# dashboard.net
KiCad netlist of a schematic drawn in EAGLE
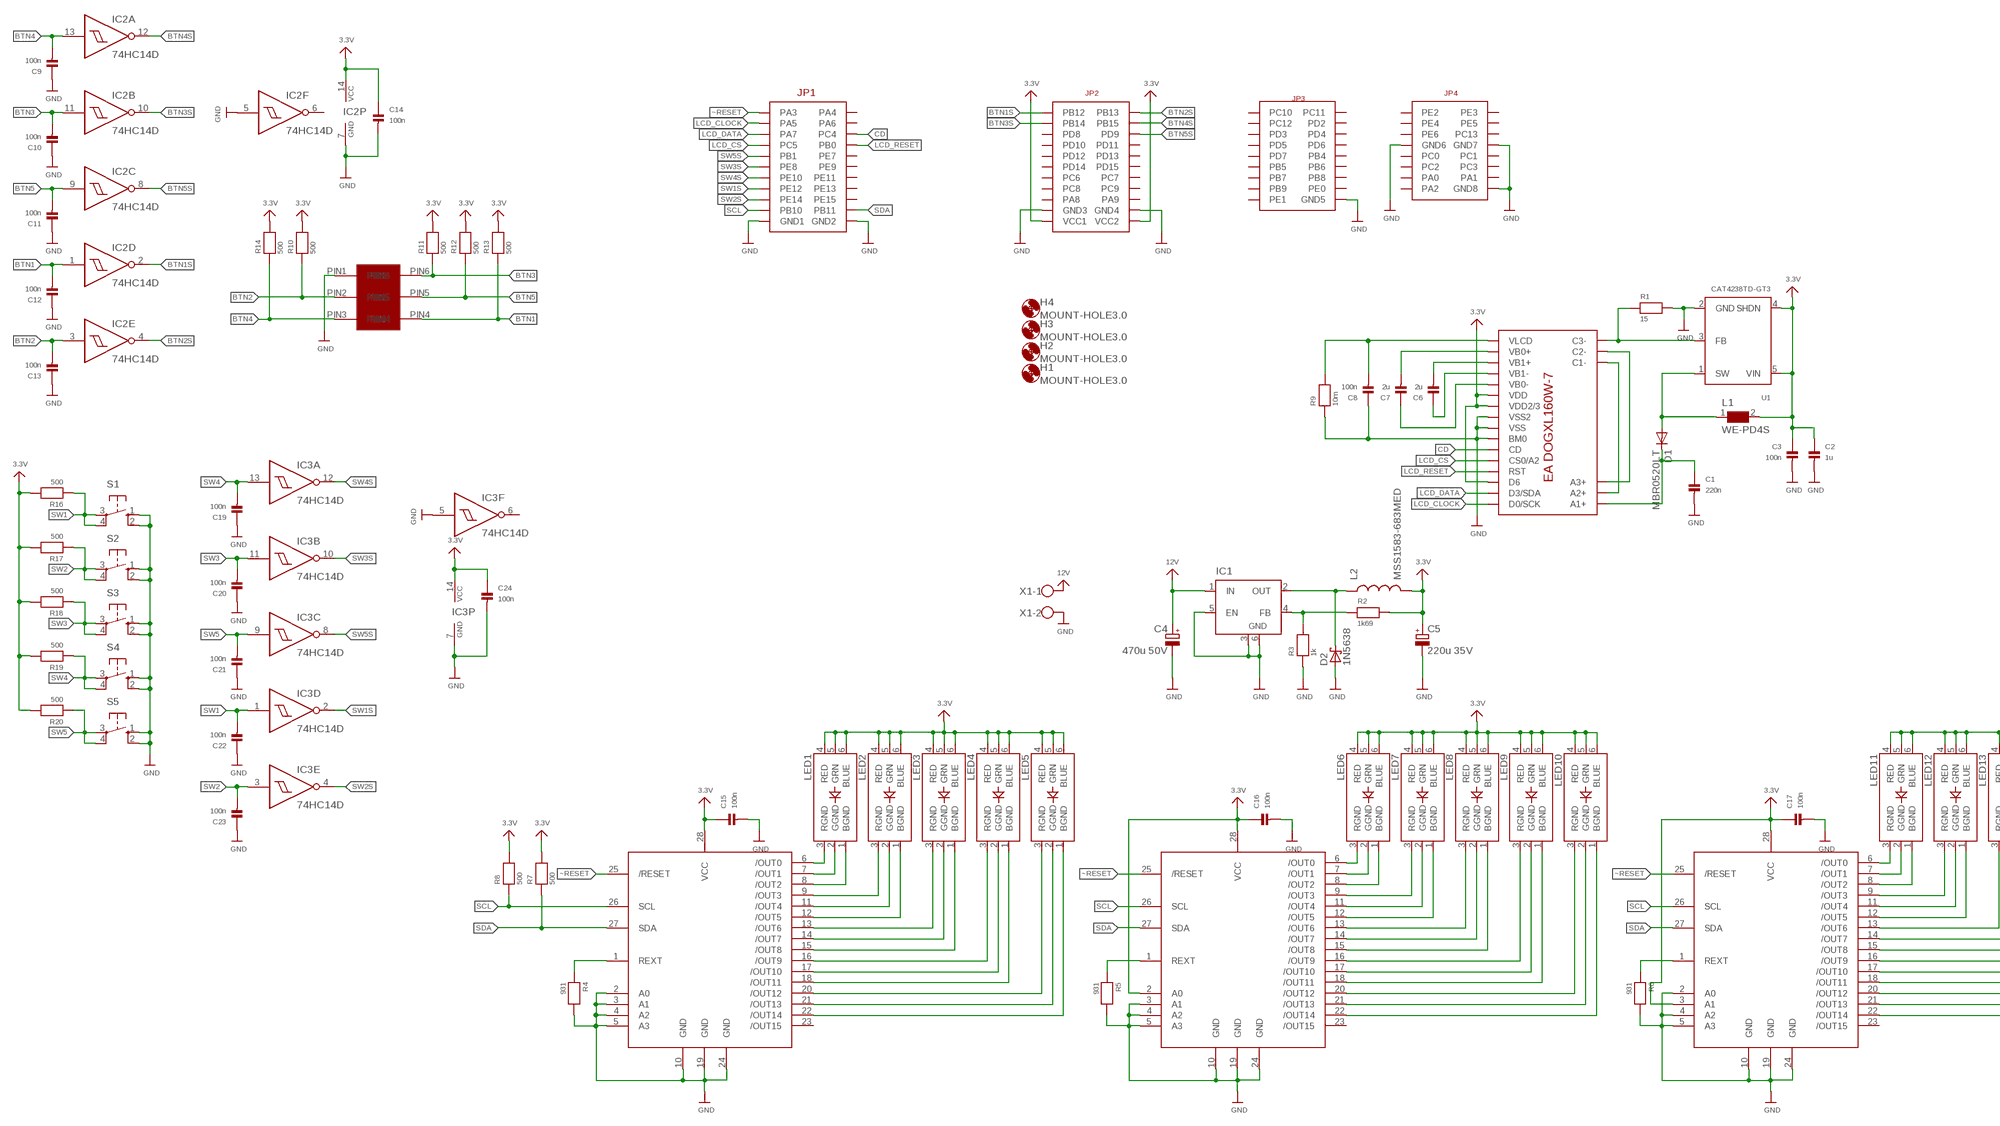
[diagram p0: schematic, sheet 1, part 1 of 2]
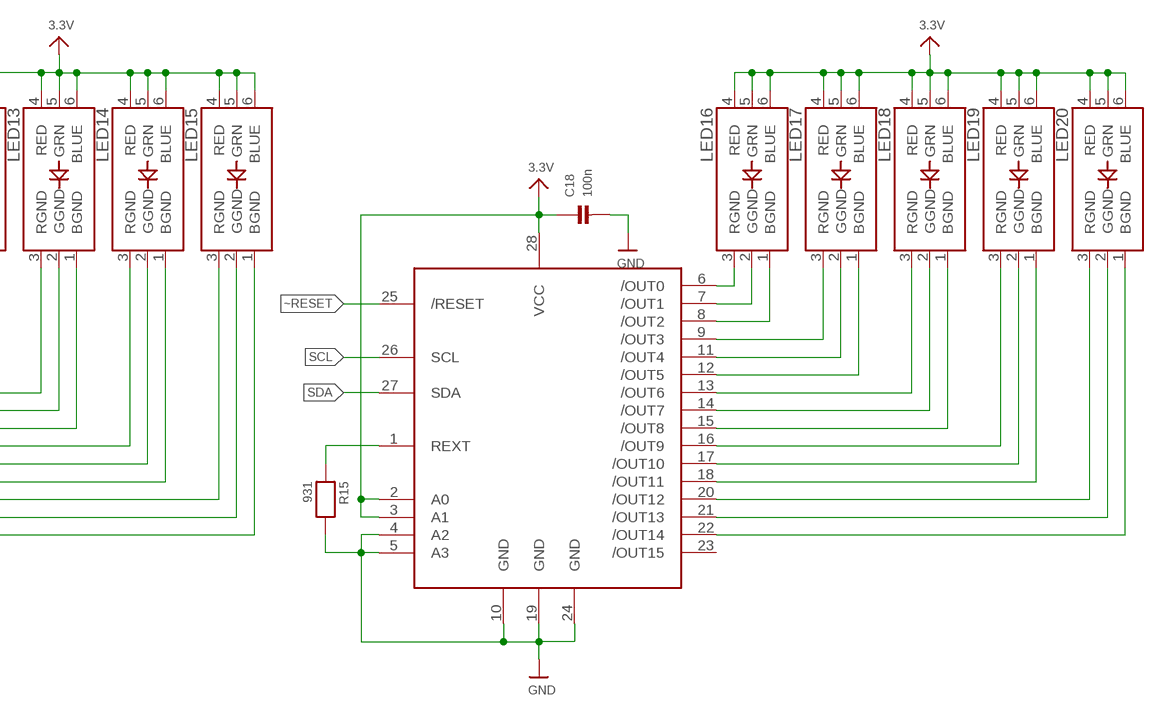
[diagram p1: schematic, sheet 1, part 2 of 2]

(export (version "E")
  (design (tool "Eeschema 10.0.6"))
  (components
    (comp (ref "C1")
      (value "220n")
      (footprint "eagle-import:_0805")
      (libsource (lib "eagle-import") (part "CAP_CERAMIC_0805"))
    )
    (comp (ref "C2")
      (value "1u")
      (footprint "eagle-import:_0805")
      (libsource (lib "eagle-import") (part "CAP_CERAMIC_0805"))
    )
    (comp (ref "C3")
      (value "100n")
      (footprint "eagle-import:_0603")
      (libsource (lib "eagle-import") (part "CAP_CERAMIC_0603"))
    )
    (comp (ref "C4")
      (value "470u 50V")
      (footprint "eagle-import:E5-13")
      (libsource (lib "eagle-import") (part "CPOL-EUE5-13"))
    )
    (comp (ref "C5")
      (value "220u 35V")
      (footprint "eagle-import:E3,5-8")
      (libsource (lib "eagle-import") (part "CPOL-EUE3.5-8"))
    )
    (comp (ref "C6")
      (value "2u")
      (footprint "eagle-import:_0805")
      (libsource (lib "eagle-import") (part "CAP_CERAMIC_0805"))
    )
    (comp (ref "C7")
      (value "2u")
      (footprint "eagle-import:_0805")
      (libsource (lib "eagle-import") (part "CAP_CERAMIC_0805"))
    )
    (comp (ref "C8")
      (value "100n")
      (footprint "eagle-import:_0603")
      (libsource (lib "eagle-import") (part "CAP_CERAMIC_0603"))
    )
    (comp (ref "C9")
      (value "100n")
      (footprint "eagle-import:_0603")
      (libsource (lib "eagle-import") (part "CAP_CERAMIC_0603"))
    )
    (comp (ref "C10")
      (value "100n")
      (footprint "eagle-import:_0603")
      (libsource (lib "eagle-import") (part "CAP_CERAMIC_0603"))
    )
    (comp (ref "C11")
      (value "100n")
      (footprint "eagle-import:_0603")
      (libsource (lib "eagle-import") (part "CAP_CERAMIC_0603"))
    )
    (comp (ref "C12")
      (value "100n")
      (footprint "eagle-import:_0603")
      (libsource (lib "eagle-import") (part "CAP_CERAMIC_0603"))
    )
    (comp (ref "C13")
      (value "100n")
      (footprint "eagle-import:_0603")
      (libsource (lib "eagle-import") (part "CAP_CERAMIC_0603"))
    )
    (comp (ref "C14")
      (value "100n")
      (footprint "eagle-import:_0603")
      (libsource (lib "eagle-import") (part "CAP_CERAMIC_0603"))
    )
    (comp (ref "C15")
      (value "100n")
      (footprint "eagle-import:_0603")
      (libsource (lib "eagle-import") (part "CAP_CERAMIC_0603"))
    )
    (comp (ref "C16")
      (value "100n")
      (footprint "eagle-import:_0603")
      (libsource (lib "eagle-import") (part "CAP_CERAMIC_0603"))
    )
    (comp (ref "C17")
      (value "100n")
      (footprint "eagle-import:_0603")
      (libsource (lib "eagle-import") (part "CAP_CERAMIC_0603"))
    )
    (comp (ref "C18")
      (value "100n")
      (footprint "eagle-import:_0603")
      (libsource (lib "eagle-import") (part "CAP_CERAMIC_0603"))
    )
    (comp (ref "C19")
      (value "100n")
      (footprint "eagle-import:_0603")
      (libsource (lib "eagle-import") (part "CAP_CERAMIC_0603"))
    )
    (comp (ref "C20")
      (value "100n")
      (footprint "eagle-import:_0603")
      (libsource (lib "eagle-import") (part "CAP_CERAMIC_0603"))
    )
    (comp (ref "C21")
      (value "100n")
      (footprint "eagle-import:_0603")
      (libsource (lib "eagle-import") (part "CAP_CERAMIC_0603"))
    )
    (comp (ref "C22")
      (value "100n")
      (footprint "eagle-import:_0603")
      (libsource (lib "eagle-import") (part "CAP_CERAMIC_0603"))
    )
    (comp (ref "C23")
      (value "100n")
      (footprint "eagle-import:_0603")
      (libsource (lib "eagle-import") (part "CAP_CERAMIC_0603"))
    )
    (comp (ref "C24")
      (value "100n")
      (footprint "eagle-import:_0603")
      (libsource (lib "eagle-import") (part "CAP_CERAMIC_0603"))
    )
    (comp (ref "D1")
      (value "MBR0520LT")
      (footprint "eagle-import:SOD123")
      (libsource (lib "eagle-import") (part "MBR0520LT"))
    )
    (comp (ref "D2")
      (value "1N5638")
      (footprint "eagle-import:DO13M")
      (libsource (lib "eagle-import") (part "1N5638"))
    )
    (comp (ref "H1")
      (value "MOUNT-HOLE3.0")
      (footprint "eagle-import:3,0")
      (libsource (lib "eagle-import") (part "MOUNT-HOLE3.0"))
    )
    (comp (ref "H2")
      (value "MOUNT-HOLE3.0")
      (footprint "eagle-import:3,0")
      (libsource (lib "eagle-import") (part "MOUNT-HOLE3.0"))
    )
    (comp (ref "H3")
      (value "MOUNT-HOLE3.0")
      (footprint "eagle-import:3,0")
      (libsource (lib "eagle-import") (part "MOUNT-HOLE3.0"))
    )
    (comp (ref "H4")
      (value "MOUNT-HOLE3.0")
      (footprint "eagle-import:3,0")
      (libsource (lib "eagle-import") (part "MOUNT-HOLE3.0"))
    )
    (comp (ref "IC1")
      (value "LM2596S")
      (footprint "eagle-import:TO263-5")
      (libsource (lib "eagle-import") (part "LM2596S"))
    )
    (comp (ref "IC2")
      (value "74HC14D")
      (footprint "eagle-import:SO14")
      (libsource (lib "eagle-import") (part "7414DHC"))
    )
    (comp (ref "IC3")
      (value "74HC14D")
      (footprint "eagle-import:SO14")
      (libsource (lib "eagle-import") (part "7414DHC"))
    )
    (comp (ref "L1")
      (value "WE-PD4S")
      (footprint "eagle-import:S")
      (fields (field (name "MPN") "7445501"))
      (libsource (lib "eagle-import") (part "WE-PD4_S-7445501"))
    )
    (comp (ref "L2")
      (value "MSS1583-683MED")
      (footprint "eagle-import:CDRH125")
      (libsource (lib "eagle-import") (part "INDUCTORPWR"))
    )
    (comp (ref "LED1")
      (value "LED_RGB_PLCC6CREE-CLV6A")
      (footprint "eagle-import:RGBLED_PLCC6")
      (libsource (lib "eagle-import") (part "LED_RGB_PLCC6CREE-CLV6A"))
    )
    (comp (ref "LED2")
      (value "LED_RGB_PLCC6CREE-CLV6A")
      (footprint "eagle-import:RGBLED_PLCC6")
      (libsource (lib "eagle-import") (part "LED_RGB_PLCC6CREE-CLV6A"))
    )
    (comp (ref "LED3")
      (value "LED_RGB_PLCC6CREE-CLV6A")
      (footprint "eagle-import:RGBLED_PLCC6")
      (libsource (lib "eagle-import") (part "LED_RGB_PLCC6CREE-CLV6A"))
    )
    (comp (ref "LED4")
      (value "LED_RGB_PLCC6CREE-CLV6A")
      (footprint "eagle-import:RGBLED_PLCC6")
      (libsource (lib "eagle-import") (part "LED_RGB_PLCC6CREE-CLV6A"))
    )
    (comp (ref "LED5")
      (value "LED_RGB_PLCC6CREE-CLV6A")
      (footprint "eagle-import:RGBLED_PLCC6")
      (libsource (lib "eagle-import") (part "LED_RGB_PLCC6CREE-CLV6A"))
    )
    (comp (ref "LED6")
      (value "LED_RGB_PLCC6CREE-CLV6A")
      (footprint "eagle-import:RGBLED_PLCC6")
      (libsource (lib "eagle-import") (part "LED_RGB_PLCC6CREE-CLV6A"))
    )
    (comp (ref "LED7")
      (value "LED_RGB_PLCC6CREE-CLV6A")
      (footprint "eagle-import:RGBLED_PLCC6")
      (libsource (lib "eagle-import") (part "LED_RGB_PLCC6CREE-CLV6A"))
    )
    (comp (ref "LED8")
      (value "LED_RGB_PLCC6CREE-CLV6A")
      (footprint "eagle-import:RGBLED_PLCC6")
      (libsource (lib "eagle-import") (part "LED_RGB_PLCC6CREE-CLV6A"))
    )
    (comp (ref "LED9")
      (value "LED_RGB_PLCC6CREE-CLV6A")
      (footprint "eagle-import:RGBLED_PLCC6")
      (libsource (lib "eagle-import") (part "LED_RGB_PLCC6CREE-CLV6A"))
    )
    (comp (ref "LED10")
      (value "LED_RGB_PLCC6CREE-CLV6A")
      (footprint "eagle-import:RGBLED_PLCC6")
      (libsource (lib "eagle-import") (part "LED_RGB_PLCC6CREE-CLV6A"))
    )
    (comp (ref "LED11")
      (value "LED_RGB_PLCC6CREE-CLV6A")
      (footprint "eagle-import:RGBLED_PLCC6")
      (libsource (lib "eagle-import") (part "LED_RGB_PLCC6CREE-CLV6A"))
    )
    (comp (ref "LED12")
      (value "LED_RGB_PLCC6CREE-CLV6A")
      (footprint "eagle-import:RGBLED_PLCC6")
      (libsource (lib "eagle-import") (part "LED_RGB_PLCC6CREE-CLV6A"))
    )
    (comp (ref "LED13")
      (value "LED_RGB_PLCC6CREE-CLV6A")
      (footprint "eagle-import:RGBLED_PLCC6")
      (libsource (lib "eagle-import") (part "LED_RGB_PLCC6CREE-CLV6A"))
    )
    (comp (ref "LED14")
      (value "LED_RGB_PLCC6CREE-CLV6A")
      (footprint "eagle-import:RGBLED_PLCC6")
      (libsource (lib "eagle-import") (part "LED_RGB_PLCC6CREE-CLV6A"))
    )
    (comp (ref "LED15")
      (value "LED_RGB_PLCC6CREE-CLV6A")
      (footprint "eagle-import:RGBLED_PLCC6")
      (libsource (lib "eagle-import") (part "LED_RGB_PLCC6CREE-CLV6A"))
    )
    (comp (ref "LED16")
      (value "LED_RGB_PLCC6CREE-CLV6A")
      (footprint "eagle-import:RGBLED_PLCC6")
      (libsource (lib "eagle-import") (part "LED_RGB_PLCC6CREE-CLV6A"))
    )
    (comp (ref "LED17")
      (value "LED_RGB_PLCC6CREE-CLV6A")
      (footprint "eagle-import:RGBLED_PLCC6")
      (libsource (lib "eagle-import") (part "LED_RGB_PLCC6CREE-CLV6A"))
    )
    (comp (ref "LED18")
      (value "LED_RGB_PLCC6CREE-CLV6A")
      (footprint "eagle-import:RGBLED_PLCC6")
      (libsource (lib "eagle-import") (part "LED_RGB_PLCC6CREE-CLV6A"))
    )
    (comp (ref "LED19")
      (value "LED_RGB_PLCC6CREE-CLV6A")
      (footprint "eagle-import:RGBLED_PLCC6")
      (libsource (lib "eagle-import") (part "LED_RGB_PLCC6CREE-CLV6A"))
    )
    (comp (ref "LED20")
      (value "LED_RGB_PLCC6CREE-CLV6A")
      (footprint "eagle-import:RGBLED_PLCC6")
      (libsource (lib "eagle-import") (part "LED_RGB_PLCC6CREE-CLV6A"))
    )
    (comp (ref "R1")
      (value "15")
      (footprint "eagle-import:_0603")
      (libsource (lib "eagle-import") (part "RESISTOR_0603"))
    )
    (comp (ref "R2")
      (value "1k69")
      (footprint "eagle-import:_0603")
      (libsource (lib "eagle-import") (part "RESISTOR_0603"))
    )
    (comp (ref "R3")
      (value "1k")
      (footprint "eagle-import:_0603")
      (libsource (lib "eagle-import") (part "RESISTOR_0603"))
    )
    (comp (ref "R4")
      (value "931")
      (footprint "eagle-import:_0603")
      (libsource (lib "eagle-import") (part "RESISTOR_0603"))
    )
    (comp (ref "R5")
      (value "931")
      (footprint "eagle-import:_0603")
      (libsource (lib "eagle-import") (part "RESISTOR_0603"))
    )
    (comp (ref "R6")
      (value "931")
      (footprint "eagle-import:_0603")
      (libsource (lib "eagle-import") (part "RESISTOR_0603"))
    )
    (comp (ref "R7")
      (value "500")
      (footprint "eagle-import:_0603")
      (libsource (lib "eagle-import") (part "RESISTOR_0603"))
    )
    (comp (ref "R8")
      (value "500")
      (footprint "eagle-import:_0603")
      (libsource (lib "eagle-import") (part "RESISTOR_0603"))
    )
    (comp (ref "R9")
      (value "10m")
      (footprint "eagle-import:_0805")
      (libsource (lib "eagle-import") (part "RESISTOR_0805"))
    )
    (comp (ref "R10")
      (value "500")
      (footprint "eagle-import:_0603")
      (libsource (lib "eagle-import") (part "RESISTOR_0603"))
    )
    (comp (ref "R11")
      (value "500")
      (footprint "eagle-import:_0603")
      (libsource (lib "eagle-import") (part "RESISTOR_0603"))
    )
    (comp (ref "R12")
      (value "500")
      (footprint "eagle-import:_0603")
      (libsource (lib "eagle-import") (part "RESISTOR_0603"))
    )
    (comp (ref "R13")
      (value "500")
      (footprint "eagle-import:_0603")
      (libsource (lib "eagle-import") (part "RESISTOR_0603"))
    )
    (comp (ref "R14")
      (value "500")
      (footprint "eagle-import:_0603")
      (libsource (lib "eagle-import") (part "RESISTOR_0603"))
    )
    (comp (ref "R15")
      (value "931")
      (footprint "eagle-import:_0603")
      (libsource (lib "eagle-import") (part "RESISTOR_0603"))
    )
    (comp (ref "R16")
      (value "500")
      (footprint "eagle-import:_0603")
      (libsource (lib "eagle-import") (part "RESISTOR_0603"))
    )
    (comp (ref "R17")
      (value "500")
      (footprint "eagle-import:_0603")
      (libsource (lib "eagle-import") (part "RESISTOR_0603"))
    )
    (comp (ref "R18")
      (value "500")
      (footprint "eagle-import:_0603")
      (libsource (lib "eagle-import") (part "RESISTOR_0603"))
    )
    (comp (ref "R19")
      (value "500")
      (footprint "eagle-import:_0603")
      (libsource (lib "eagle-import") (part "RESISTOR_0603"))
    )
    (comp (ref "R20")
      (value "500")
      (footprint "eagle-import:_0603")
      (libsource (lib "eagle-import") (part "RESISTOR_0603"))
    )
    (comp (ref "S1")
      (value "10-XX")
      (footprint "eagle-import:B3F-10XX")
      (fields (field (name "MPN") "B3F-1000"))
      (libsource (lib "eagle-import") (part "10-XX"))
    )
    (comp (ref "S2")
      (value "10-XX")
      (footprint "eagle-import:B3F-10XX")
      (fields (field (name "MPN") "B3F-1000"))
      (libsource (lib "eagle-import") (part "10-XX"))
    )
    (comp (ref "S3")
      (value "10-XX")
      (footprint "eagle-import:B3F-10XX")
      (fields (field (name "MPN") "B3F-1000"))
      (libsource (lib "eagle-import") (part "10-XX"))
    )
    (comp (ref "S4")
      (value "10-XX")
      (footprint "eagle-import:B3F-10XX")
      (fields (field (name "MPN") "B3F-1000"))
      (libsource (lib "eagle-import") (part "10-XX"))
    )
    (comp (ref "S5")
      (value "10-XX")
      (footprint "eagle-import:B3F-10XX")
      (fields
        (field (name "MPN") "B3F-1000")
        (field (name "MPN_1") "B3F-1000")
        (field (name "OC_FARNELL") "176432")
        (field (name "OC_NEWARK") "36M3542")
      )
      (libsource (lib "eagle-import") (part "10-XX"))
    )
    (comp (ref "U$1")
      (value "CPU-BOARD")
      (footprint "eagle-import:CPU-BOARD-JP1")
      (libsource (lib "eagle-import") (part "CPU-BOARD"))
    )
    (comp (ref "U$10")
      (value "EA-DOGXL160W-7")
      (footprint "eagle-import:EA-DOGXL160W-7")
      (libsource (lib "eagle-import") (part "EA-DOGXL160W-7"))
    )
    (comp (ref "U$30")
      (value "TLC59116")
      (footprint "eagle-import:TSSOP28")
      (libsource (lib "eagle-import") (part "TLC59116"))
    )
    (comp (ref "U$33")
      (value "TLC59116")
      (footprint "eagle-import:TSSOP28")
      (libsource (lib "eagle-import") (part "TLC59116"))
    )
    (comp (ref "U$36")
      (value "TLC59116")
      (footprint "eagle-import:TSSOP28")
      (libsource (lib "eagle-import") (part "TLC59116"))
    )
    (comp (ref "U$42")
      (value "MICROFIT6")
      (footprint "eagle-import:MICROFIT6SOCK")
      (libsource (lib "eagle-import") (part "MICROFIT6"))
    )
    (comp (ref "U$51")
      (value "TLC59116")
      (footprint "eagle-import:TSSOP28")
      (libsource (lib "eagle-import") (part "TLC59116"))
    )
    (comp (ref "U1")
      (value "CAT4238TD-GT3")
      (footprint "eagle-import:SOT23-5")
      (libsource (lib "eagle-import") (part "FAN5331"))
    )
    (comp (ref "X1")
      (value "W237-102")
      (footprint "eagle-import:W237-102")
      (fields (field (name "MPN") "237-102"))
      (libsource (lib "eagle-import") (part "W237-102"))
    )
  )
  (nets
    (net (code "1") (name "/~{RESET}") (class "Default")
      (node (ref "U$1") (pin "P$1") (pinfunction "PA3_P$1") (pintype "bidirectional"))
      (node (ref "U$30") (pin "25") (pinfunction "/RESET_25") (pintype "bidirectional"))
      (node (ref "U$33") (pin "25") (pinfunction "/RESET_25") (pintype "bidirectional"))
      (node (ref "U$36") (pin "25") (pinfunction "/RESET_25") (pintype "bidirectional"))
      (node (ref "U$51") (pin "25") (pinfunction "/RESET_25") (pintype "bidirectional"))
    )
    (net (code "2") (name "3.3V") (class "Default")
      (node (ref "C14") (pin "1") (pinfunction "P$1_1") (pintype "passive"))
      (node (ref "C15") (pin "1") (pinfunction "P$1_1") (pintype "passive"))
      (node (ref "C16") (pin "1") (pinfunction "P$1_1") (pintype "passive"))
      (node (ref "C17") (pin "1") (pinfunction "P$1_1") (pintype "passive"))
      (node (ref "C18") (pin "1") (pinfunction "P$1_1") (pintype "passive"))
      (node (ref "C2") (pin "1") (pinfunction "P$1_1") (pintype "passive"))
      (node (ref "C24") (pin "1") (pinfunction "P$1_1") (pintype "passive"))
      (node (ref "C3") (pin "1") (pinfunction "P$1_1") (pintype "passive"))
      (node (ref "C5") (pin "+") (pinfunction "+_+") (pintype "passive"))
      (node (ref "IC2") (pin "14") (pinfunction "VCC_14") (pintype "power_in"))
      (node (ref "IC3") (pin "14") (pinfunction "VCC_14") (pintype "power_in"))
      (node (ref "L1") (pin "2") (pinfunction "2_2") (pintype "passive"))
      (node (ref "L2") (pin "2") (pinfunction "2_2") (pintype "passive"))
      (node (ref "LED1") (pin "4") (pinfunction "RED_4") (pintype "bidirectional"))
      (node (ref "LED1") (pin "5") (pinfunction "GRN_5") (pintype "bidirectional"))
      (node (ref "LED1") (pin "6") (pinfunction "BLUE_6") (pintype "bidirectional"))
      (node (ref "LED10") (pin "4") (pinfunction "RED_4") (pintype "bidirectional"))
      (node (ref "LED10") (pin "5") (pinfunction "GRN_5") (pintype "bidirectional"))
      (node (ref "LED10") (pin "6") (pinfunction "BLUE_6") (pintype "bidirectional"))
      (node (ref "LED11") (pin "4") (pinfunction "RED_4") (pintype "bidirectional"))
      (node (ref "LED11") (pin "5") (pinfunction "GRN_5") (pintype "bidirectional"))
      (node (ref "LED11") (pin "6") (pinfunction "BLUE_6") (pintype "bidirectional"))
      (node (ref "LED12") (pin "4") (pinfunction "RED_4") (pintype "bidirectional"))
      (node (ref "LED12") (pin "5") (pinfunction "GRN_5") (pintype "bidirectional"))
      (node (ref "LED12") (pin "6") (pinfunction "BLUE_6") (pintype "bidirectional"))
      (node (ref "LED13") (pin "4") (pinfunction "RED_4") (pintype "bidirectional"))
      (node (ref "LED13") (pin "5") (pinfunction "GRN_5") (pintype "bidirectional"))
      (node (ref "LED13") (pin "6") (pinfunction "BLUE_6") (pintype "bidirectional"))
      (node (ref "LED14") (pin "4") (pinfunction "RED_4") (pintype "bidirectional"))
      (node (ref "LED14") (pin "5") (pinfunction "GRN_5") (pintype "bidirectional"))
      (node (ref "LED14") (pin "6") (pinfunction "BLUE_6") (pintype "bidirectional"))
      (node (ref "LED15") (pin "4") (pinfunction "RED_4") (pintype "bidirectional"))
      (node (ref "LED15") (pin "5") (pinfunction "GRN_5") (pintype "bidirectional"))
      (node (ref "LED15") (pin "6") (pinfunction "BLUE_6") (pintype "bidirectional"))
      (node (ref "LED16") (pin "4") (pinfunction "RED_4") (pintype "bidirectional"))
      (node (ref "LED16") (pin "5") (pinfunction "GRN_5") (pintype "bidirectional"))
      (node (ref "LED16") (pin "6") (pinfunction "BLUE_6") (pintype "bidirectional"))
      (node (ref "LED17") (pin "4") (pinfunction "RED_4") (pintype "bidirectional"))
      (node (ref "LED17") (pin "5") (pinfunction "GRN_5") (pintype "bidirectional"))
      (node (ref "LED17") (pin "6") (pinfunction "BLUE_6") (pintype "bidirectional"))
      (node (ref "LED18") (pin "4") (pinfunction "RED_4") (pintype "bidirectional"))
      (node (ref "LED18") (pin "5") (pinfunction "GRN_5") (pintype "bidirectional"))
      (node (ref "LED18") (pin "6") (pinfunction "BLUE_6") (pintype "bidirectional"))
      (node (ref "LED19") (pin "4") (pinfunction "RED_4") (pintype "bidirectional"))
      (node (ref "LED19") (pin "5") (pinfunction "GRN_5") (pintype "bidirectional"))
      (node (ref "LED19") (pin "6") (pinfunction "BLUE_6") (pintype "bidirectional"))
      (node (ref "LED2") (pin "4") (pinfunction "RED_4") (pintype "bidirectional"))
      (node (ref "LED2") (pin "5") (pinfunction "GRN_5") (pintype "bidirectional"))
      (node (ref "LED2") (pin "6") (pinfunction "BLUE_6") (pintype "bidirectional"))
      (node (ref "LED20") (pin "4") (pinfunction "RED_4") (pintype "bidirectional"))
      (node (ref "LED20") (pin "5") (pinfunction "GRN_5") (pintype "bidirectional"))
      (node (ref "LED20") (pin "6") (pinfunction "BLUE_6") (pintype "bidirectional"))
      (node (ref "LED3") (pin "4") (pinfunction "RED_4") (pintype "bidirectional"))
      (node (ref "LED3") (pin "5") (pinfunction "GRN_5") (pintype "bidirectional"))
      (node (ref "LED3") (pin "6") (pinfunction "BLUE_6") (pintype "bidirectional"))
      (node (ref "LED4") (pin "4") (pinfunction "RED_4") (pintype "bidirectional"))
      (node (ref "LED4") (pin "5") (pinfunction "GRN_5") (pintype "bidirectional"))
      (node (ref "LED4") (pin "6") (pinfunction "BLUE_6") (pintype "bidirectional"))
      (node (ref "LED5") (pin "4") (pinfunction "RED_4") (pintype "bidirectional"))
      (node (ref "LED5") (pin "5") (pinfunction "GRN_5") (pintype "bidirectional"))
      (node (ref "LED5") (pin "6") (pinfunction "BLUE_6") (pintype "bidirectional"))
      (node (ref "LED6") (pin "4") (pinfunction "RED_4") (pintype "bidirectional"))
      (node (ref "LED6") (pin "5") (pinfunction "GRN_5") (pintype "bidirectional"))
      (node (ref "LED6") (pin "6") (pinfunction "BLUE_6") (pintype "bidirectional"))
      (node (ref "LED7") (pin "4") (pinfunction "RED_4") (pintype "bidirectional"))
      (node (ref "LED7") (pin "5") (pinfunction "GRN_5") (pintype "bidirectional"))
      (node (ref "LED7") (pin "6") (pinfunction "BLUE_6") (pintype "bidirectional"))
      (node (ref "LED8") (pin "4") (pinfunction "RED_4") (pintype "bidirectional"))
      (node (ref "LED8") (pin "5") (pinfunction "GRN_5") (pintype "bidirectional"))
      (node (ref "LED8") (pin "6") (pinfunction "BLUE_6") (pintype "bidirectional"))
      (node (ref "LED9") (pin "4") (pinfunction "RED_4") (pintype "bidirectional"))
      (node (ref "LED9") (pin "5") (pinfunction "GRN_5") (pintype "bidirectional"))
      (node (ref "LED9") (pin "6") (pinfunction "BLUE_6") (pintype "bidirectional"))
      (node (ref "R10") (pin "2") (pinfunction "2_2") (pintype "passive"))
      (node (ref "R11") (pin "2") (pinfunction "2_2") (pintype "passive"))
      (node (ref "R12") (pin "2") (pinfunction "2_2") (pintype "passive"))
      (node (ref "R13") (pin "2") (pinfunction "2_2") (pintype "passive"))
      (node (ref "R14") (pin "2") (pinfunction "2_2") (pintype "passive"))
      (node (ref "R16") (pin "2") (pinfunction "2_2") (pintype "passive"))
      (node (ref "R17") (pin "2") (pinfunction "2_2") (pintype "passive"))
      (node (ref "R18") (pin "2") (pinfunction "2_2") (pintype "passive"))
      (node (ref "R19") (pin "2") (pinfunction "2_2") (pintype "passive"))
      (node (ref "R2") (pin "2") (pinfunction "2_2") (pintype "passive"))
      (node (ref "R20") (pin "2") (pinfunction "2_2") (pintype "passive"))
      (node (ref "R7") (pin "2") (pinfunction "2_2") (pintype "passive"))
      (node (ref "R8") (pin "2") (pinfunction "2_2") (pintype "passive"))
      (node (ref "U$1") (pin "P$43") (pinfunction "VCC1_P$43") (pintype "bidirectional"))
      (node (ref "U$1") (pin "P$44") (pinfunction "VCC2_P$44") (pintype "bidirectional"))
      (node (ref "U$10") (pin "P$22") (pinfunction "VDD_P$22") (pintype "bidirectional"))
      (node (ref "U$10") (pin "P$23") (pinfunction "VDD2/3_P$23") (pintype "bidirectional"))
      (node (ref "U$10") (pin "P$30") (pinfunction "D6_P$30") (pintype "bidirectional"))
      (node (ref "U$30") (pin "28") (pinfunction "VCC_28") (pintype "bidirectional"))
      (node (ref "U$33") (pin "2") (pinfunction "A0_2") (pintype "bidirectional"))
      (node (ref "U$33") (pin "28") (pinfunction "VCC_28") (pintype "bidirectional"))
      (node (ref "U$36") (pin "28") (pinfunction "VCC_28") (pintype "bidirectional"))
      (node (ref "U$36") (pin "3") (pinfunction "A1_3") (pintype "bidirectional"))
      (node (ref "U$51") (pin "2") (pinfunction "A0_2") (pintype "bidirectional"))
      (node (ref "U$51") (pin "28") (pinfunction "VCC_28") (pintype "bidirectional"))
      (node (ref "U$51") (pin "3") (pinfunction "A1_3") (pintype "bidirectional"))
      (node (ref "U1") (pin "4") (pinfunction "SHDN_4") (pintype "bidirectional"))
      (node (ref "U1") (pin "5") (pinfunction "VIN_5") (pintype "bidirectional"))
    )
    (net (code "3") (name "12V") (class "Default")
      (node (ref "C4") (pin "+") (pinfunction "+_+") (pintype "passive"))
      (node (ref "IC1") (pin "1") (pinfunction "IN_1") (pintype "input"))
      (node (ref "X1") (pin "1") (pinfunction "KL_1") (pintype "passive"))
    )
    (net (code "4") (name "BTN1") (class "Default")
      (node (ref "C12") (pin "2") (pinfunction "P$2_2") (pintype "passive"))
      (node (ref "IC2") (pin "1") (pinfunction "I_1") (pintype "input"))
      (node (ref "R13") (pin "1") (pinfunction "1_1") (pintype "passive"))
      (node (ref "U$42") (pin "PIN4") (pinfunction "PIN4_PIN4") (pintype "bidirectional"))
    )
    (net (code "5") (name "BTN1S") (class "Default")
      (node (ref "IC2") (pin "2") (pinfunction "O_2") (pintype "output"))
      (node (ref "U$1") (pin "P$23") (pinfunction "PB12_P$23") (pintype "bidirectional"))
    )
    (net (code "6") (name "BTN2") (class "Default")
      (node (ref "C13") (pin "2") (pinfunction "P$2_2") (pintype "passive"))
      (node (ref "IC2") (pin "3") (pinfunction "I_3") (pintype "input"))
      (node (ref "R10") (pin "1") (pinfunction "1_1") (pintype "passive"))
      (node (ref "U$42") (pin "PIN2") (pinfunction "PIN2_PIN2") (pintype "bidirectional"))
    )
    (net (code "7") (name "BTN2S") (class "Default")
      (node (ref "IC2") (pin "4") (pinfunction "O_4") (pintype "output"))
      (node (ref "U$1") (pin "P$24") (pinfunction "PB13_P$24") (pintype "bidirectional"))
    )
    (net (code "8") (name "BTN3") (class "Default")
      (node (ref "C10") (pin "2") (pinfunction "P$2_2") (pintype "passive"))
      (node (ref "IC2") (pin "11") (pinfunction "I_11") (pintype "input"))
      (node (ref "R11") (pin "1") (pinfunction "1_1") (pintype "passive"))
      (node (ref "U$42") (pin "PIN6") (pinfunction "PIN6_PIN6") (pintype "bidirectional"))
    )
    (net (code "9") (name "BTN3S") (class "Default")
      (node (ref "IC2") (pin "10") (pinfunction "O_10") (pintype "output"))
      (node (ref "U$1") (pin "P$25") (pinfunction "PB14_P$25") (pintype "bidirectional"))
    )
    (net (code "10") (name "BTN4") (class "Default")
      (node (ref "C9") (pin "2") (pinfunction "P$2_2") (pintype "passive"))
      (node (ref "IC2") (pin "13") (pinfunction "I_13") (pintype "input"))
      (node (ref "R14") (pin "1") (pinfunction "1_1") (pintype "passive"))
      (node (ref "U$42") (pin "PIN3") (pinfunction "PIN3_PIN3") (pintype "bidirectional"))
    )
    (net (code "11") (name "BTN4S") (class "Default")
      (node (ref "IC2") (pin "12") (pinfunction "O_12") (pintype "output"))
      (node (ref "U$1") (pin "P$26") (pinfunction "PB15_P$26") (pintype "bidirectional"))
    )
    (net (code "12") (name "BTN5") (class "Default")
      (node (ref "C11") (pin "2") (pinfunction "P$2_2") (pintype "passive"))
      (node (ref "IC2") (pin "9") (pinfunction "I_9") (pintype "input"))
      (node (ref "R12") (pin "1") (pinfunction "1_1") (pintype "passive"))
      (node (ref "U$42") (pin "PIN5") (pinfunction "PIN5_PIN5") (pintype "bidirectional"))
    )
    (net (code "13") (name "BTN5S") (class "Default")
      (node (ref "IC2") (pin "8") (pinfunction "O_8") (pintype "output"))
      (node (ref "U$1") (pin "P$28") (pinfunction "PD9_P$28") (pintype "bidirectional"))
    )
    (net (code "14") (name "CD") (class "Default")
      (node (ref "U$1") (pin "P$6") (pinfunction "PC4_P$6") (pintype "bidirectional"))
      (node (ref "U$10") (pin "P$27") (pinfunction "CD_P$27") (pintype "bidirectional"))
    )
    (net (code "15") (name "GND") (class "Default")
      (node (ref "C1") (pin "2") (pinfunction "P$2_2") (pintype "passive"))
      (node (ref "C10") (pin "1") (pinfunction "P$1_1") (pintype "passive"))
      (node (ref "C11") (pin "1") (pinfunction "P$1_1") (pintype "passive"))
      (node (ref "C12") (pin "1") (pinfunction "P$1_1") (pintype "passive"))
      (node (ref "C13") (pin "1") (pinfunction "P$1_1") (pintype "passive"))
      (node (ref "C14") (pin "2") (pinfunction "P$2_2") (pintype "passive"))
      (node (ref "C15") (pin "2") (pinfunction "P$2_2") (pintype "passive"))
      (node (ref "C16") (pin "2") (pinfunction "P$2_2") (pintype "passive"))
      (node (ref "C17") (pin "2") (pinfunction "P$2_2") (pintype "passive"))
      (node (ref "C18") (pin "2") (pinfunction "P$2_2") (pintype "passive"))
      (node (ref "C19") (pin "1") (pinfunction "P$1_1") (pintype "passive"))
      (node (ref "C2") (pin "2") (pinfunction "P$2_2") (pintype "passive"))
      (node (ref "C20") (pin "1") (pinfunction "P$1_1") (pintype "passive"))
      (node (ref "C21") (pin "1") (pinfunction "P$1_1") (pintype "passive"))
      (node (ref "C22") (pin "1") (pinfunction "P$1_1") (pintype "passive"))
      (node (ref "C23") (pin "1") (pinfunction "P$1_1") (pintype "passive"))
      (node (ref "C24") (pin "2") (pinfunction "P$2_2") (pintype "passive"))
      (node (ref "C3") (pin "2") (pinfunction "P$2_2") (pintype "passive"))
      (node (ref "C4") (pin "-") (pinfunction "-_-") (pintype "passive"))
      (node (ref "C5") (pin "-") (pinfunction "-_-") (pintype "passive"))
      (node (ref "C8") (pin "1") (pinfunction "P$1_1") (pintype "passive"))
      (node (ref "C9") (pin "1") (pinfunction "P$1_1") (pintype "passive"))
      (node (ref "D2") (pin "A") (pinfunction "A_A") (pintype "passive"))
      (node (ref "IC1") (pin "3") (pinfunction "GND_3") (pintype "power_in"))
      (node (ref "IC1") (pin "5") (pinfunction "EN_5") (pintype "input"))
      (node (ref "IC1") (pin "6") (pinfunction "GND_6") (pintype "power_in"))
      (node (ref "IC2") (pin "5") (pinfunction "I_5") (pintype "input"))
      (node (ref "IC2") (pin "7") (pinfunction "GND_7") (pintype "power_in"))
      (node (ref "IC3") (pin "5") (pinfunction "I_5") (pintype "input"))
      (node (ref "IC3") (pin "7") (pinfunction "GND_7") (pintype "power_in"))
      (node (ref "R1") (pin "2") (pinfunction "2_2") (pintype "passive"))
      (node (ref "R15") (pin "2") (pinfunction "2_2") (pintype "passive"))
      (node (ref "R3") (pin "1") (pinfunction "1_1") (pintype "passive"))
      (node (ref "R4") (pin "2") (pinfunction "2_2") (pintype "passive"))
      (node (ref "R5") (pin "2") (pinfunction "2_2") (pintype "passive"))
      (node (ref "R6") (pin "2") (pinfunction "2_2") (pintype "passive"))
      (node (ref "R9") (pin "1") (pinfunction "1_1") (pintype "passive"))
      (node (ref "S1") (pin "1") (pinfunction "S_1") (pintype "passive"))
      (node (ref "S1") (pin "2") (pinfunction "S1_2") (pintype "passive"))
      (node (ref "S2") (pin "1") (pinfunction "S_1") (pintype "passive"))
      (node (ref "S2") (pin "2") (pinfunction "S1_2") (pintype "passive"))
      (node (ref "S3") (pin "1") (pinfunction "S_1") (pintype "passive"))
      (node (ref "S3") (pin "2") (pinfunction "S1_2") (pintype "passive"))
      (node (ref "S4") (pin "1") (pinfunction "S_1") (pintype "passive"))
      (node (ref "S4") (pin "2") (pinfunction "S1_2") (pintype "passive"))
      (node (ref "S5") (pin "1") (pinfunction "S_1") (pintype "passive"))
      (node (ref "S5") (pin "2") (pinfunction "S1_2") (pintype "passive"))
      (node (ref "U$1") (pin "P$21") (pinfunction "GND1_P$21") (pintype "bidirectional"))
      (node (ref "U$1") (pin "P$22") (pinfunction "GND2_P$22") (pintype "bidirectional"))
      (node (ref "U$1") (pin "P$41") (pinfunction "GND3_P$41") (pintype "bidirectional"))
      (node (ref "U$1") (pin "P$42") (pinfunction "GND4_P$42") (pintype "bidirectional"))
      (node (ref "U$1") (pin "P$62") (pinfunction "GND5_P$62") (pintype "bidirectional"))
      (node (ref "U$1") (pin "P$69") (pinfunction "GND6_P$69") (pintype "bidirectional"))
      (node (ref "U$1") (pin "P$70") (pinfunction "GND7_P$70") (pintype "bidirectional"))
      (node (ref "U$1") (pin "P$78") (pinfunction "GND8_P$78") (pintype "bidirectional"))
      (node (ref "U$10") (pin "P$24") (pinfunction "VSS2_P$24") (pintype "bidirectional"))
      (node (ref "U$10") (pin "P$25") (pinfunction "VSS_P$25") (pintype "bidirectional"))
      (node (ref "U$10") (pin "P$26") (pinfunction "BM0_P$26") (pintype "bidirectional"))
      (node (ref "U$30") (pin "10") (pinfunction "GND_10") (pintype "bidirectional"))
      (node (ref "U$30") (pin "19") (pinfunction "GND_19") (pintype "bidirectional"))
      (node (ref "U$30") (pin "2") (pinfunction "A0_2") (pintype "bidirectional"))
      (node (ref "U$30") (pin "24") (pinfunction "GND_24") (pintype "bidirectional"))
      (node (ref "U$30") (pin "3") (pinfunction "A1_3") (pintype "bidirectional"))
      (node (ref "U$30") (pin "4") (pinfunction "A2_4") (pintype "bidirectional"))
      (node (ref "U$30") (pin "5") (pinfunction "A3_5") (pintype "bidirectional"))
      (node (ref "U$33") (pin "10") (pinfunction "GND_10") (pintype "bidirectional"))
      (node (ref "U$33") (pin "19") (pinfunction "GND_19") (pintype "bidirectional"))
      (node (ref "U$33") (pin "24") (pinfunction "GND_24") (pintype "bidirectional"))
      (node (ref "U$33") (pin "3") (pinfunction "A1_3") (pintype "bidirectional"))
      (node (ref "U$33") (pin "4") (pinfunction "A2_4") (pintype "bidirectional"))
      (node (ref "U$33") (pin "5") (pinfunction "A3_5") (pintype "bidirectional"))
      (node (ref "U$36") (pin "10") (pinfunction "GND_10") (pintype "bidirectional"))
      (node (ref "U$36") (pin "19") (pinfunction "GND_19") (pintype "bidirectional"))
      (node (ref "U$36") (pin "2") (pinfunction "A0_2") (pintype "bidirectional"))
      (node (ref "U$36") (pin "24") (pinfunction "GND_24") (pintype "bidirectional"))
      (node (ref "U$36") (pin "4") (pinfunction "A2_4") (pintype "bidirectional"))
      (node (ref "U$36") (pin "5") (pinfunction "A3_5") (pintype "bidirectional"))
      (node (ref "U$42") (pin "PIN1") (pinfunction "PIN1_PIN1") (pintype "bidirectional"))
      (node (ref "U$51") (pin "10") (pinfunction "GND_10") (pintype "bidirectional"))
      (node (ref "U$51") (pin "19") (pinfunction "GND_19") (pintype "bidirectional"))
      (node (ref "U$51") (pin "24") (pinfunction "GND_24") (pintype "bidirectional"))
      (node (ref "U$51") (pin "4") (pinfunction "A2_4") (pintype "bidirectional"))
      (node (ref "U$51") (pin "5") (pinfunction "A3_5") (pintype "bidirectional"))
      (node (ref "U1") (pin "2") (pinfunction "GND_2") (pintype "bidirectional"))
      (node (ref "X1") (pin "2") (pinfunction "KL_2") (pintype "passive"))
    )
    (net (code "16") (name "LCD_CLOCK") (class "Default")
      (node (ref "U$1") (pin "P$3") (pinfunction "PA5_P$3") (pintype "bidirectional"))
      (node (ref "U$10") (pin "P$32") (pinfunction "D0/SCK_P$32") (pintype "bidirectional"))
    )
    (net (code "17") (name "LCD_CS") (class "Default")
      (node (ref "U$1") (pin "P$7") (pinfunction "PC5_P$7") (pintype "bidirectional"))
      (node (ref "U$10") (pin "P$28") (pinfunction "CS0/A2_P$28") (pintype "bidirectional"))
    )
    (net (code "18") (name "LCD_DATA") (class "Default")
      (node (ref "U$1") (pin "P$5") (pinfunction "PA7_P$5") (pintype "bidirectional"))
      (node (ref "U$10") (pin "P$31") (pinfunction "D3/SDA_P$31") (pintype "bidirectional"))
    )
    (net (code "19") (name "LCD_RESET") (class "Default")
      (node (ref "U$1") (pin "P$8") (pinfunction "PB0_P$8") (pintype "bidirectional"))
      (node (ref "U$10") (pin "P$29") (pinfunction "RST_P$29") (pintype "bidirectional"))
    )
    (net (code "20") (name "Net-(C1-P$1)") (class "Default")
      (node (ref "C1") (pin "1") (pinfunction "P$1_1") (pintype "passive"))
      (node (ref "D1") (pin "C") (pinfunction "C_C") (pintype "passive"))
      (node (ref "U$10") (pin "P$1") (pinfunction "A1+_P$1") (pintype "bidirectional"))
    )
    (net (code "21") (name "Net-(C6-P$1)") (class "Default")
      (node (ref "C6") (pin "1") (pinfunction "P$1_1") (pintype "passive"))
      (node (ref "U$10") (pin "P$20") (pinfunction "VB1-_P$20") (pintype "bidirectional"))
    )
    (net (code "22") (name "Net-(C6-P$2)") (class "Default")
      (node (ref "C6") (pin "2") (pinfunction "P$2_2") (pintype "passive"))
      (node (ref "U$10") (pin "P$19") (pinfunction "VB1+_P$19") (pintype "bidirectional"))
    )
    (net (code "23") (name "Net-(C7-P$1)") (class "Default")
      (node (ref "C7") (pin "1") (pinfunction "P$1_1") (pintype "passive"))
      (node (ref "U$10") (pin "P$21") (pinfunction "VB0-_P$21") (pintype "bidirectional"))
    )
    (net (code "24") (name "Net-(C7-P$2)") (class "Default")
      (node (ref "C7") (pin "2") (pinfunction "P$2_2") (pintype "passive"))
      (node (ref "U$10") (pin "P$18") (pinfunction "VB0+_P$18") (pintype "bidirectional"))
    )
    (net (code "25") (name "Net-(C8-P$2)") (class "Default")
      (node (ref "C8") (pin "2") (pinfunction "P$2_2") (pintype "passive"))
      (node (ref "R9") (pin "2") (pinfunction "2_2") (pintype "passive"))
      (node (ref "U$10") (pin "P$17") (pinfunction "VLCD_P$17") (pintype "bidirectional"))
    )
    (net (code "26") (name "Net-(IC1-FB)") (class "Default")
      (node (ref "IC1") (pin "4") (pinfunction "FB_4") (pintype "input"))
      (node (ref "R2") (pin "1") (pinfunction "1_1") (pintype "passive"))
      (node (ref "R3") (pin "2") (pinfunction "2_2") (pintype "passive"))
    )
    (net (code "27") (name "Net-(IC1-OUT)") (class "Default")
      (node (ref "D2") (pin "C") (pinfunction "C_C") (pintype "passive"))
      (node (ref "IC1") (pin "2") (pinfunction "OUT_2") (pintype "output"))
      (node (ref "L2") (pin "1") (pinfunction "1_1") (pintype "passive"))
    )
    (net (code "28") (name "Net-(LED1-BGND)") (class "Default")
      (node (ref "LED1") (pin "1") (pinfunction "BGND_1") (pintype "power_in"))
      (node (ref "U$30") (pin "8") (pinfunction "/OUT2_8") (pintype "bidirectional"))
    )
    (net (code "29") (name "Net-(LED1-GGND)") (class "Default")
      (node (ref "LED1") (pin "2") (pinfunction "GGND_2") (pintype "power_in"))
      (node (ref "U$30") (pin "7") (pinfunction "/OUT1_7") (pintype "bidirectional"))
    )
    (net (code "30") (name "Net-(LED1-RGND)") (class "Default")
      (node (ref "LED1") (pin "3") (pinfunction "RGND_3") (pintype "power_in"))
      (node (ref "U$30") (pin "6") (pinfunction "/OUT0_6") (pintype "bidirectional"))
    )
    (net (code "31") (name "Net-(LED2-BGND)") (class "Default")
      (node (ref "LED2") (pin "1") (pinfunction "BGND_1") (pintype "power_in"))
      (node (ref "U$30") (pin "12") (pinfunction "/OUT5_12") (pintype "bidirectional"))
    )
    (net (code "32") (name "Net-(LED2-GGND)") (class "Default")
      (node (ref "LED2") (pin "2") (pinfunction "GGND_2") (pintype "power_in"))
      (node (ref "U$30") (pin "11") (pinfunction "/OUT4_11") (pintype "bidirectional"))
    )
    (net (code "33") (name "Net-(LED2-RGND)") (class "Default")
      (node (ref "LED2") (pin "3") (pinfunction "RGND_3") (pintype "power_in"))
      (node (ref "U$30") (pin "9") (pinfunction "/OUT3_9") (pintype "bidirectional"))
    )
    (net (code "34") (name "Net-(LED3-BGND)") (class "Default")
      (node (ref "LED3") (pin "1") (pinfunction "BGND_1") (pintype "power_in"))
      (node (ref "U$30") (pin "15") (pinfunction "/OUT8_15") (pintype "bidirectional"))
    )
    (net (code "35") (name "Net-(LED3-GGND)") (class "Default")
      (node (ref "LED3") (pin "2") (pinfunction "GGND_2") (pintype "power_in"))
      (node (ref "U$30") (pin "14") (pinfunction "/OUT7_14") (pintype "bidirectional"))
    )
    (net (code "36") (name "Net-(LED3-RGND)") (class "Default")
      (node (ref "LED3") (pin "3") (pinfunction "RGND_3") (pintype "power_in"))
      (node (ref "U$30") (pin "13") (pinfunction "/OUT6_13") (pintype "bidirectional"))
    )
    (net (code "37") (name "Net-(LED4-BGND)") (class "Default")
      (node (ref "LED4") (pin "1") (pinfunction "BGND_1") (pintype "power_in"))
      (node (ref "U$30") (pin "18") (pinfunction "/OUT11_18") (pintype "bidirectional"))
    )
    (net (code "38") (name "Net-(LED4-GGND)") (class "Default")
      (node (ref "LED4") (pin "2") (pinfunction "GGND_2") (pintype "power_in"))
      (node (ref "U$30") (pin "17") (pinfunction "/OUT10_17") (pintype "bidirectional"))
    )
    (net (code "39") (name "Net-(LED4-RGND)") (class "Default")
      (node (ref "LED4") (pin "3") (pinfunction "RGND_3") (pintype "power_in"))
      (node (ref "U$30") (pin "16") (pinfunction "/OUT9_16") (pintype "bidirectional"))
    )
    (net (code "40") (name "Net-(LED5-BGND)") (class "Default")
      (node (ref "LED5") (pin "1") (pinfunction "BGND_1") (pintype "power_in"))
      (node (ref "U$30") (pin "22") (pinfunction "/OUT14_22") (pintype "bidirectional"))
    )
    (net (code "41") (name "Net-(LED5-GGND)") (class "Default")
      (node (ref "LED5") (pin "2") (pinfunction "GGND_2") (pintype "power_in"))
      (node (ref "U$30") (pin "21") (pinfunction "/OUT13_21") (pintype "bidirectional"))
    )
    (net (code "42") (name "Net-(LED5-RGND)") (class "Default")
      (node (ref "LED5") (pin "3") (pinfunction "RGND_3") (pintype "power_in"))
      (node (ref "U$30") (pin "20") (pinfunction "/OUT12_20") (pintype "bidirectional"))
    )
    (net (code "43") (name "Net-(LED6-BGND)") (class "Default")
      (node (ref "LED6") (pin "1") (pinfunction "BGND_1") (pintype "power_in"))
      (node (ref "U$33") (pin "8") (pinfunction "/OUT2_8") (pintype "bidirectional"))
    )
    (net (code "44") (name "Net-(LED6-GGND)") (class "Default")
      (node (ref "LED6") (pin "2") (pinfunction "GGND_2") (pintype "power_in"))
      (node (ref "U$33") (pin "7") (pinfunction "/OUT1_7") (pintype "bidirectional"))
    )
    (net (code "45") (name "Net-(LED6-RGND)") (class "Default")
      (node (ref "LED6") (pin "3") (pinfunction "RGND_3") (pintype "power_in"))
      (node (ref "U$33") (pin "6") (pinfunction "/OUT0_6") (pintype "bidirectional"))
    )
    (net (code "46") (name "Net-(LED7-BGND)") (class "Default")
      (node (ref "LED7") (pin "1") (pinfunction "BGND_1") (pintype "power_in"))
      (node (ref "U$33") (pin "12") (pinfunction "/OUT5_12") (pintype "bidirectional"))
    )
    (net (code "47") (name "Net-(LED7-GGND)") (class "Default")
      (node (ref "LED7") (pin "2") (pinfunction "GGND_2") (pintype "power_in"))
      (node (ref "U$33") (pin "11") (pinfunction "/OUT4_11") (pintype "bidirectional"))
    )
    (net (code "48") (name "Net-(LED7-RGND)") (class "Default")
      (node (ref "LED7") (pin "3") (pinfunction "RGND_3") (pintype "power_in"))
      (node (ref "U$33") (pin "9") (pinfunction "/OUT3_9") (pintype "bidirectional"))
    )
    (net (code "49") (name "Net-(LED8-BGND)") (class "Default")
      (node (ref "LED8") (pin "1") (pinfunction "BGND_1") (pintype "power_in"))
      (node (ref "U$33") (pin "15") (pinfunction "/OUT8_15") (pintype "bidirectional"))
    )
    (net (code "50") (name "Net-(LED8-GGND)") (class "Default")
      (node (ref "LED8") (pin "2") (pinfunction "GGND_2") (pintype "power_in"))
      (node (ref "U$33") (pin "14") (pinfunction "/OUT7_14") (pintype "bidirectional"))
    )
    (net (code "51") (name "Net-(LED8-RGND)") (class "Default")
      (node (ref "LED8") (pin "3") (pinfunction "RGND_3") (pintype "power_in"))
      (node (ref "U$33") (pin "13") (pinfunction "/OUT6_13") (pintype "bidirectional"))
    )
    (net (code "52") (name "Net-(LED9-BGND)") (class "Default")
      (node (ref "LED9") (pin "1") (pinfunction "BGND_1") (pintype "power_in"))
      (node (ref "U$33") (pin "18") (pinfunction "/OUT11_18") (pintype "bidirectional"))
    )
    (net (code "53") (name "Net-(LED9-GGND)") (class "Default")
      (node (ref "LED9") (pin "2") (pinfunction "GGND_2") (pintype "power_in"))
      (node (ref "U$33") (pin "17") (pinfunction "/OUT10_17") (pintype "bidirectional"))
    )
    (net (code "54") (name "Net-(LED9-RGND)") (class "Default")
      (node (ref "LED9") (pin "3") (pinfunction "RGND_3") (pintype "power_in"))
      (node (ref "U$33") (pin "16") (pinfunction "/OUT9_16") (pintype "bidirectional"))
    )
    (net (code "55") (name "Net-(LED10-BGND)") (class "Default")
      (node (ref "LED10") (pin "1") (pinfunction "BGND_1") (pintype "power_in"))
      (node (ref "U$33") (pin "22") (pinfunction "/OUT14_22") (pintype "bidirectional"))
    )
    (net (code "56") (name "Net-(LED10-GGND)") (class "Default")
      (node (ref "LED10") (pin "2") (pinfunction "GGND_2") (pintype "power_in"))
      (node (ref "U$33") (pin "21") (pinfunction "/OUT13_21") (pintype "bidirectional"))
    )
    (net (code "57") (name "Net-(LED10-RGND)") (class "Default")
      (node (ref "LED10") (pin "3") (pinfunction "RGND_3") (pintype "power_in"))
      (node (ref "U$33") (pin "20") (pinfunction "/OUT12_20") (pintype "bidirectional"))
    )
    (net (code "58") (name "Net-(LED11-BGND)") (class "Default")
      (node (ref "LED11") (pin "1") (pinfunction "BGND_1") (pintype "power_in"))
      (node (ref "U$36") (pin "8") (pinfunction "/OUT2_8") (pintype "bidirectional"))
    )
    (net (code "59") (name "Net-(LED11-GGND)") (class "Default")
      (node (ref "LED11") (pin "2") (pinfunction "GGND_2") (pintype "power_in"))
      (node (ref "U$36") (pin "7") (pinfunction "/OUT1_7") (pintype "bidirectional"))
    )
    (net (code "60") (name "Net-(LED11-RGND)") (class "Default")
      (node (ref "LED11") (pin "3") (pinfunction "RGND_3") (pintype "power_in"))
      (node (ref "U$36") (pin "6") (pinfunction "/OUT0_6") (pintype "bidirectional"))
    )
    (net (code "61") (name "Net-(LED12-BGND)") (class "Default")
      (node (ref "LED12") (pin "1") (pinfunction "BGND_1") (pintype "power_in"))
      (node (ref "U$36") (pin "12") (pinfunction "/OUT5_12") (pintype "bidirectional"))
    )
    (net (code "62") (name "Net-(LED12-GGND)") (class "Default")
      (node (ref "LED12") (pin "2") (pinfunction "GGND_2") (pintype "power_in"))
      (node (ref "U$36") (pin "11") (pinfunction "/OUT4_11") (pintype "bidirectional"))
    )
    (net (code "63") (name "Net-(LED12-RGND)") (class "Default")
      (node (ref "LED12") (pin "3") (pinfunction "RGND_3") (pintype "power_in"))
      (node (ref "U$36") (pin "9") (pinfunction "/OUT3_9") (pintype "bidirectional"))
    )
    (net (code "64") (name "Net-(LED13-BGND)") (class "Default")
      (node (ref "LED13") (pin "1") (pinfunction "BGND_1") (pintype "power_in"))
      (node (ref "U$36") (pin "15") (pinfunction "/OUT8_15") (pintype "bidirectional"))
    )
    (net (code "65") (name "Net-(LED13-GGND)") (class "Default")
      (node (ref "LED13") (pin "2") (pinfunction "GGND_2") (pintype "power_in"))
      (node (ref "U$36") (pin "14") (pinfunction "/OUT7_14") (pintype "bidirectional"))
    )
    (net (code "66") (name "Net-(LED13-RGND)") (class "Default")
      (node (ref "LED13") (pin "3") (pinfunction "RGND_3") (pintype "power_in"))
      (node (ref "U$36") (pin "13") (pinfunction "/OUT6_13") (pintype "bidirectional"))
    )
    (net (code "67") (name "Net-(LED14-BGND)") (class "Default")
      (node (ref "LED14") (pin "1") (pinfunction "BGND_1") (pintype "power_in"))
      (node (ref "U$36") (pin "18") (pinfunction "/OUT11_18") (pintype "bidirectional"))
    )
    (net (code "68") (name "Net-(LED14-GGND)") (class "Default")
      (node (ref "LED14") (pin "2") (pinfunction "GGND_2") (pintype "power_in"))
      (node (ref "U$36") (pin "17") (pinfunction "/OUT10_17") (pintype "bidirectional"))
    )
    (net (code "69") (name "Net-(LED14-RGND)") (class "Default")
      (node (ref "LED14") (pin "3") (pinfunction "RGND_3") (pintype "power_in"))
      (node (ref "U$36") (pin "16") (pinfunction "/OUT9_16") (pintype "bidirectional"))
    )
    (net (code "70") (name "Net-(LED15-BGND)") (class "Default")
      (node (ref "LED15") (pin "1") (pinfunction "BGND_1") (pintype "power_in"))
      (node (ref "U$36") (pin "22") (pinfunction "/OUT14_22") (pintype "bidirectional"))
    )
    (net (code "71") (name "Net-(LED15-GGND)") (class "Default")
      (node (ref "LED15") (pin "2") (pinfunction "GGND_2") (pintype "power_in"))
      (node (ref "U$36") (pin "21") (pinfunction "/OUT13_21") (pintype "bidirectional"))
    )
    (net (code "72") (name "Net-(LED15-RGND)") (class "Default")
      (node (ref "LED15") (pin "3") (pinfunction "RGND_3") (pintype "power_in"))
      (node (ref "U$36") (pin "20") (pinfunction "/OUT12_20") (pintype "bidirectional"))
    )
    (net (code "73") (name "Net-(LED16-BGND)") (class "Default")
      (node (ref "LED16") (pin "1") (pinfunction "BGND_1") (pintype "power_in"))
      (node (ref "U$51") (pin "8") (pinfunction "/OUT2_8") (pintype "bidirectional"))
    )
    (net (code "74") (name "Net-(LED16-GGND)") (class "Default")
      (node (ref "LED16") (pin "2") (pinfunction "GGND_2") (pintype "power_in"))
      (node (ref "U$51") (pin "7") (pinfunction "/OUT1_7") (pintype "bidirectional"))
    )
    (net (code "75") (name "Net-(LED16-RGND)") (class "Default")
      (node (ref "LED16") (pin "3") (pinfunction "RGND_3") (pintype "power_in"))
      (node (ref "U$51") (pin "6") (pinfunction "/OUT0_6") (pintype "bidirectional"))
    )
    (net (code "76") (name "Net-(LED17-BGND)") (class "Default")
      (node (ref "LED17") (pin "1") (pinfunction "BGND_1") (pintype "power_in"))
      (node (ref "U$51") (pin "12") (pinfunction "/OUT5_12") (pintype "bidirectional"))
    )
    (net (code "77") (name "Net-(LED17-GGND)") (class "Default")
      (node (ref "LED17") (pin "2") (pinfunction "GGND_2") (pintype "power_in"))
      (node (ref "U$51") (pin "11") (pinfunction "/OUT4_11") (pintype "bidirectional"))
    )
    (net (code "78") (name "Net-(LED17-RGND)") (class "Default")
      (node (ref "LED17") (pin "3") (pinfunction "RGND_3") (pintype "power_in"))
      (node (ref "U$51") (pin "9") (pinfunction "/OUT3_9") (pintype "bidirectional"))
    )
    (net (code "79") (name "Net-(LED18-BGND)") (class "Default")
      (node (ref "LED18") (pin "1") (pinfunction "BGND_1") (pintype "power_in"))
      (node (ref "U$51") (pin "15") (pinfunction "/OUT8_15") (pintype "bidirectional"))
    )
    (net (code "80") (name "Net-(LED18-GGND)") (class "Default")
      (node (ref "LED18") (pin "2") (pinfunction "GGND_2") (pintype "power_in"))
      (node (ref "U$51") (pin "14") (pinfunction "/OUT7_14") (pintype "bidirectional"))
    )
    (net (code "81") (name "Net-(LED18-RGND)") (class "Default")
      (node (ref "LED18") (pin "3") (pinfunction "RGND_3") (pintype "power_in"))
      (node (ref "U$51") (pin "13") (pinfunction "/OUT6_13") (pintype "bidirectional"))
    )
    (net (code "82") (name "Net-(LED19-BGND)") (class "Default")
      (node (ref "LED19") (pin "1") (pinfunction "BGND_1") (pintype "power_in"))
      (node (ref "U$51") (pin "18") (pinfunction "/OUT11_18") (pintype "bidirectional"))
    )
    (net (code "83") (name "Net-(LED19-GGND)") (class "Default")
      (node (ref "LED19") (pin "2") (pinfunction "GGND_2") (pintype "power_in"))
      (node (ref "U$51") (pin "17") (pinfunction "/OUT10_17") (pintype "bidirectional"))
    )
    (net (code "84") (name "Net-(LED19-RGND)") (class "Default")
      (node (ref "LED19") (pin "3") (pinfunction "RGND_3") (pintype "power_in"))
      (node (ref "U$51") (pin "16") (pinfunction "/OUT9_16") (pintype "bidirectional"))
    )
    (net (code "85") (name "Net-(LED20-BGND)") (class "Default")
      (node (ref "LED20") (pin "1") (pinfunction "BGND_1") (pintype "power_in"))
      (node (ref "U$51") (pin "22") (pinfunction "/OUT14_22") (pintype "bidirectional"))
    )
    (net (code "86") (name "Net-(LED20-GGND)") (class "Default")
      (node (ref "LED20") (pin "2") (pinfunction "GGND_2") (pintype "power_in"))
      (node (ref "U$51") (pin "21") (pinfunction "/OUT13_21") (pintype "bidirectional"))
    )
    (net (code "87") (name "Net-(LED20-RGND)") (class "Default")
      (node (ref "LED20") (pin "3") (pinfunction "RGND_3") (pintype "power_in"))
      (node (ref "U$51") (pin "20") (pinfunction "/OUT12_20") (pintype "bidirectional"))
    )
    (net (code "88") (name "Net-(U$10-A2+)") (class "Default")
      (node (ref "U$10") (pin "P$14") (pinfunction "C1-_P$14") (pintype "bidirectional"))
      (node (ref "U$10") (pin "P$2") (pinfunction "A2+_P$2") (pintype "bidirectional"))
    )
    (net (code "89") (name "Net-(U$10-A3+)") (class "Default")
      (node (ref "U$10") (pin "P$15") (pinfunction "C2-_P$15") (pintype "bidirectional"))
      (node (ref "U$10") (pin "P$3") (pinfunction "A3+_P$3") (pintype "bidirectional"))
    )
    (net (code "90") (name "Net-(U$10-C3-)") (class "Default")
      (node (ref "R1") (pin "1") (pinfunction "1_1") (pintype "passive"))
      (node (ref "U$10") (pin "P$16") (pinfunction "C3-_P$16") (pintype "bidirectional"))
      (node (ref "U1") (pin "3") (pinfunction "FB_3") (pintype "bidirectional"))
    )
    (net (code "91") (name "Net-(U$30-REXT)") (class "Default")
      (node (ref "R4") (pin "1") (pinfunction "1_1") (pintype "passive"))
      (node (ref "U$30") (pin "1") (pinfunction "REXT_1") (pintype "bidirectional"))
    )
    (net (code "92") (name "Net-(U$33-REXT)") (class "Default")
      (node (ref "R5") (pin "1") (pinfunction "1_1") (pintype "passive"))
      (node (ref "U$33") (pin "1") (pinfunction "REXT_1") (pintype "bidirectional"))
    )
    (net (code "93") (name "Net-(U$36-REXT)") (class "Default")
      (node (ref "R6") (pin "1") (pinfunction "1_1") (pintype "passive"))
      (node (ref "U$36") (pin "1") (pinfunction "REXT_1") (pintype "bidirectional"))
    )
    (net (code "94") (name "Net-(U$51-REXT)") (class "Default")
      (node (ref "R15") (pin "1") (pinfunction "1_1") (pintype "passive"))
      (node (ref "U$51") (pin "1") (pinfunction "REXT_1") (pintype "bidirectional"))
    )
    (net (code "95") (name "Net-(U1-SW)") (class "Default")
      (node (ref "D1") (pin "A") (pinfunction "A_A") (pintype "passive"))
      (node (ref "L1") (pin "1") (pinfunction "1_1") (pintype "passive"))
      (node (ref "U1") (pin "1") (pinfunction "SW_1") (pintype "bidirectional"))
    )
    (net (code "96") (name "SCL") (class "Default")
      (node (ref "R8") (pin "1") (pinfunction "1_1") (pintype "passive"))
      (node (ref "U$1") (pin "P$19") (pinfunction "PB10_P$19") (pintype "bidirectional"))
      (node (ref "U$30") (pin "26") (pinfunction "SCL_26") (pintype "bidirectional"))
      (node (ref "U$33") (pin "26") (pinfunction "SCL_26") (pintype "bidirectional"))
      (node (ref "U$36") (pin "26") (pinfunction "SCL_26") (pintype "bidirectional"))
      (node (ref "U$51") (pin "26") (pinfunction "SCL_26") (pintype "bidirectional"))
    )
    (net (code "97") (name "SDA") (class "Default")
      (node (ref "R7") (pin "1") (pinfunction "1_1") (pintype "passive"))
      (node (ref "U$1") (pin "P$20") (pinfunction "PB11_P$20") (pintype "bidirectional"))
      (node (ref "U$30") (pin "27") (pinfunction "SDA_27") (pintype "bidirectional"))
      (node (ref "U$33") (pin "27") (pinfunction "SDA_27") (pintype "bidirectional"))
      (node (ref "U$36") (pin "27") (pinfunction "SDA_27") (pintype "bidirectional"))
      (node (ref "U$51") (pin "27") (pinfunction "SDA_27") (pintype "bidirectional"))
    )
    (net (code "98") (name "SW1") (class "Default")
      (node (ref "C22") (pin "2") (pinfunction "P$2_2") (pintype "passive"))
      (node (ref "IC3") (pin "1") (pinfunction "I_1") (pintype "input"))
      (node (ref "R16") (pin "1") (pinfunction "1_1") (pintype "passive"))
      (node (ref "S1") (pin "3") (pinfunction "P_3") (pintype "passive"))
      (node (ref "S1") (pin "4") (pinfunction "P1_4") (pintype "passive"))
    )
    (net (code "99") (name "SW1S") (class "Default")
      (node (ref "IC3") (pin "2") (pinfunction "O_2") (pintype "output"))
      (node (ref "U$1") (pin "P$15") (pinfunction "PE12_P$15") (pintype "bidirectional"))
    )
    (net (code "100") (name "SW2") (class "Default")
      (node (ref "C23") (pin "2") (pinfunction "P$2_2") (pintype "passive"))
      (node (ref "IC3") (pin "3") (pinfunction "I_3") (pintype "input"))
      (node (ref "R17") (pin "1") (pinfunction "1_1") (pintype "passive"))
      (node (ref "S2") (pin "3") (pinfunction "P_3") (pintype "passive"))
      (node (ref "S2") (pin "4") (pinfunction "P1_4") (pintype "passive"))
    )
    (net (code "101") (name "SW2S") (class "Default")
      (node (ref "IC3") (pin "4") (pinfunction "O_4") (pintype "output"))
      (node (ref "U$1") (pin "P$17") (pinfunction "PE14_P$17") (pintype "bidirectional"))
    )
    (net (code "102") (name "SW3") (class "Default")
      (node (ref "C20") (pin "2") (pinfunction "P$2_2") (pintype "passive"))
      (node (ref "IC3") (pin "11") (pinfunction "I_11") (pintype "input"))
      (node (ref "R18") (pin "1") (pinfunction "1_1") (pintype "passive"))
      (node (ref "S3") (pin "3") (pinfunction "P_3") (pintype "passive"))
      (node (ref "S3") (pin "4") (pinfunction "P1_4") (pintype "passive"))
    )
    (net (code "103") (name "SW3S") (class "Default")
      (node (ref "IC3") (pin "10") (pinfunction "O_10") (pintype "output"))
      (node (ref "U$1") (pin "P$11") (pinfunction "PE8_P$11") (pintype "bidirectional"))
    )
    (net (code "104") (name "SW4") (class "Default")
      (node (ref "C19") (pin "2") (pinfunction "P$2_2") (pintype "passive"))
      (node (ref "IC3") (pin "13") (pinfunction "I_13") (pintype "input"))
      (node (ref "R19") (pin "1") (pinfunction "1_1") (pintype "passive"))
      (node (ref "S4") (pin "3") (pinfunction "P_3") (pintype "passive"))
      (node (ref "S4") (pin "4") (pinfunction "P1_4") (pintype "passive"))
    )
    (net (code "105") (name "SW4S") (class "Default")
      (node (ref "IC3") (pin "12") (pinfunction "O_12") (pintype "output"))
      (node (ref "U$1") (pin "P$13") (pinfunction "PE10_P$13") (pintype "bidirectional"))
    )
    (net (code "106") (name "SW5") (class "Default")
      (node (ref "C21") (pin "2") (pinfunction "P$2_2") (pintype "passive"))
      (node (ref "IC3") (pin "9") (pinfunction "I_9") (pintype "input"))
      (node (ref "R20") (pin "1") (pinfunction "1_1") (pintype "passive"))
      (node (ref "S5") (pin "3") (pinfunction "P_3") (pintype "passive"))
      (node (ref "S5") (pin "4") (pinfunction "P1_4") (pintype "passive"))
    )
    (net (code "107") (name "SW5S") (class "Default")
      (node (ref "IC3") (pin "8") (pinfunction "O_8") (pintype "output"))
      (node (ref "U$1") (pin "P$9") (pinfunction "PB1_P$9") (pintype "bidirectional"))
    )
    (net (code "108") (name "unconnected-(IC2F-O-Pad6)") (class "Default")
      (node (ref "IC2") (pin "6") (pinfunction "O_6") (pintype "output"))
    )
    (net (code "109") (name "unconnected-(IC3F-O-Pad6)") (class "Default")
      (node (ref "IC3") (pin "6") (pinfunction "O_6") (pintype "output"))
    )
    (net (code "110") (name "unconnected-(U$1A-PA4-PadP$2)") (class "Default")
      (node (ref "U$1") (pin "P$2") (pinfunction "PA4_P$2") (pintype "bidirectional"))
    )
    (net (code "111") (name "unconnected-(U$1A-PA6-PadP$4)") (class "Default")
      (node (ref "U$1") (pin "P$4") (pinfunction "PA6_P$4") (pintype "bidirectional"))
    )
    (net (code "112") (name "unconnected-(U$1A-PE7-PadP$10)") (class "Default")
      (node (ref "U$1") (pin "P$10") (pinfunction "PE7_P$10") (pintype "bidirectional"))
    )
    (net (code "113") (name "unconnected-(U$1A-PE9-PadP$12)") (class "Default")
      (node (ref "U$1") (pin "P$12") (pinfunction "PE9_P$12") (pintype "bidirectional"))
    )
    (net (code "114") (name "unconnected-(U$1A-PE11-PadP$14)") (class "Default")
      (node (ref "U$1") (pin "P$14") (pinfunction "PE11_P$14") (pintype "bidirectional"))
    )
    (net (code "115") (name "unconnected-(U$1A-PE13-PadP$16)") (class "Default")
      (node (ref "U$1") (pin "P$16") (pinfunction "PE13_P$16") (pintype "bidirectional"))
    )
    (net (code "116") (name "unconnected-(U$1A-PE15-PadP$18)") (class "Default")
      (node (ref "U$1") (pin "P$18") (pinfunction "PE15_P$18") (pintype "bidirectional"))
    )
    (net (code "117") (name "unconnected-(U$1B-PA8-PadP$39)") (class "Default")
      (node (ref "U$1") (pin "P$39") (pinfunction "PA8_P$39") (pintype "bidirectional"))
    )
    (net (code "118") (name "unconnected-(U$1B-PA9-PadP$40)") (class "Default")
      (node (ref "U$1") (pin "P$40") (pinfunction "PA9_P$40") (pintype "bidirectional"))
    )
    (net (code "119") (name "unconnected-(U$1B-PC6-PadP$35)") (class "Default")
      (node (ref "U$1") (pin "P$35") (pinfunction "PC6_P$35") (pintype "bidirectional"))
    )
    (net (code "120") (name "unconnected-(U$1B-PC7-PadP$36)") (class "Default")
      (node (ref "U$1") (pin "P$36") (pinfunction "PC7_P$36") (pintype "bidirectional"))
    )
    (net (code "121") (name "unconnected-(U$1B-PC8-PadP$37)") (class "Default")
      (node (ref "U$1") (pin "P$37") (pinfunction "PC8_P$37") (pintype "bidirectional"))
    )
    (net (code "122") (name "unconnected-(U$1B-PC9-PadP$38)") (class "Default")
      (node (ref "U$1") (pin "P$38") (pinfunction "PC9_P$38") (pintype "bidirectional"))
    )
    (net (code "123") (name "unconnected-(U$1B-PD8-PadP$27)") (class "Default")
      (node (ref "U$1") (pin "P$27") (pinfunction "PD8_P$27") (pintype "bidirectional"))
    )
    (net (code "124") (name "unconnected-(U$1B-PD10-PadP$29)") (class "Default")
      (node (ref "U$1") (pin "P$29") (pinfunction "PD10_P$29") (pintype "bidirectional"))
    )
    (net (code "125") (name "unconnected-(U$1B-PD11-PadP$30)") (class "Default")
      (node (ref "U$1") (pin "P$30") (pinfunction "PD11_P$30") (pintype "bidirectional"))
    )
    (net (code "126") (name "unconnected-(U$1B-PD12-PadP$31)") (class "Default")
      (node (ref "U$1") (pin "P$31") (pinfunction "PD12_P$31") (pintype "bidirectional"))
    )
    (net (code "127") (name "unconnected-(U$1B-PD13-PadP$32)") (class "Default")
      (node (ref "U$1") (pin "P$32") (pinfunction "PD13_P$32") (pintype "bidirectional"))
    )
    (net (code "128") (name "unconnected-(U$1B-PD14-PadP$33)") (class "Default")
      (node (ref "U$1") (pin "P$33") (pinfunction "PD14_P$33") (pintype "bidirectional"))
    )
    (net (code "129") (name "unconnected-(U$1B-PD15-PadP$34)") (class "Default")
      (node (ref "U$1") (pin "P$34") (pinfunction "PD15_P$34") (pintype "bidirectional"))
    )
    (net (code "130") (name "unconnected-(U$1C-PB4-PadP$54)") (class "Default")
      (node (ref "U$1") (pin "P$54") (pinfunction "PB4_P$54") (pintype "bidirectional"))
    )
    (net (code "131") (name "unconnected-(U$1C-PB5-PadP$55)") (class "Default")
      (node (ref "U$1") (pin "P$55") (pinfunction "PB5_P$55") (pintype "bidirectional"))
    )
    (net (code "132") (name "unconnected-(U$1C-PB6-PadP$56)") (class "Default")
      (node (ref "U$1") (pin "P$56") (pinfunction "PB6_P$56") (pintype "bidirectional"))
    )
    (net (code "133") (name "unconnected-(U$1C-PB7-PadP$57)") (class "Default")
      (node (ref "U$1") (pin "P$57") (pinfunction "PB7_P$57") (pintype "bidirectional"))
    )
    (net (code "134") (name "unconnected-(U$1C-PB8-PadP$58)") (class "Default")
      (node (ref "U$1") (pin "P$58") (pinfunction "PB8_P$58") (pintype "bidirectional"))
    )
    (net (code "135") (name "unconnected-(U$1C-PB9-PadP$59)") (class "Default")
      (node (ref "U$1") (pin "P$59") (pinfunction "PB9_P$59") (pintype "bidirectional"))
    )
    (net (code "136") (name "unconnected-(U$1C-PC10-PadP$45)") (class "Default")
      (node (ref "U$1") (pin "P$45") (pinfunction "PC10_P$45") (pintype "bidirectional"))
    )
    (net (code "137") (name "unconnected-(U$1C-PC11-PadP$46)") (class "Default")
      (node (ref "U$1") (pin "P$46") (pinfunction "PC11_P$46") (pintype "bidirectional"))
    )
    (net (code "138") (name "unconnected-(U$1C-PC12-PadP$47)") (class "Default")
      (node (ref "U$1") (pin "P$47") (pinfunction "PC12_P$47") (pintype "bidirectional"))
    )
    (net (code "139") (name "unconnected-(U$1C-PD2-PadP$48)") (class "Default")
      (node (ref "U$1") (pin "P$48") (pinfunction "PD2_P$48") (pintype "bidirectional"))
    )
    (net (code "140") (name "unconnected-(U$1C-PD3-PadP$49)") (class "Default")
      (node (ref "U$1") (pin "P$49") (pinfunction "PD3_P$49") (pintype "bidirectional"))
    )
    (net (code "141") (name "unconnected-(U$1C-PD4-PadP$50)") (class "Default")
      (node (ref "U$1") (pin "P$50") (pinfunction "PD4_P$50") (pintype "bidirectional"))
    )
    (net (code "142") (name "unconnected-(U$1C-PD5-PadP$51)") (class "Default")
      (node (ref "U$1") (pin "P$51") (pinfunction "PD5_P$51") (pintype "bidirectional"))
    )
    (net (code "143") (name "unconnected-(U$1C-PD6-PadP$52)") (class "Default")
      (node (ref "U$1") (pin "P$52") (pinfunction "PD6_P$52") (pintype "bidirectional"))
    )
    (net (code "144") (name "unconnected-(U$1C-PD7-PadP$53)") (class "Default")
      (node (ref "U$1") (pin "P$53") (pinfunction "PD7_P$53") (pintype "bidirectional"))
    )
    (net (code "145") (name "unconnected-(U$1C-PE0-PadP$60)") (class "Default")
      (node (ref "U$1") (pin "P$60") (pinfunction "PE0_P$60") (pintype "bidirectional"))
    )
    (net (code "146") (name "unconnected-(U$1C-PE1-PadP$61)") (class "Default")
      (node (ref "U$1") (pin "P$61") (pinfunction "PE1_P$61") (pintype "bidirectional"))
    )
    (net (code "147") (name "unconnected-(U$1D-PA0-PadP$75)") (class "Default")
      (node (ref "U$1") (pin "P$75") (pinfunction "PA0_P$75") (pintype "bidirectional"))
    )
    (net (code "148") (name "unconnected-(U$1D-PA1-PadP$76)") (class "Default")
      (node (ref "U$1") (pin "P$76") (pinfunction "PA1_P$76") (pintype "bidirectional"))
    )
    (net (code "149") (name "unconnected-(U$1D-PA2-PadP$77)") (class "Default")
      (node (ref "U$1") (pin "P$77") (pinfunction "PA2_P$77") (pintype "bidirectional"))
    )
    (net (code "150") (name "unconnected-(U$1D-PC0-PadP$71)") (class "Default")
      (node (ref "U$1") (pin "P$71") (pinfunction "PC0_P$71") (pintype "bidirectional"))
    )
    (net (code "151") (name "unconnected-(U$1D-PC1-PadP$72)") (class "Default")
      (node (ref "U$1") (pin "P$72") (pinfunction "PC1_P$72") (pintype "bidirectional"))
    )
    (net (code "152") (name "unconnected-(U$1D-PC2-PadP$73)") (class "Default")
      (node (ref "U$1") (pin "P$73") (pinfunction "PC2_P$73") (pintype "bidirectional"))
    )
    (net (code "153") (name "unconnected-(U$1D-PC3-PadP$74)") (class "Default")
      (node (ref "U$1") (pin "P$74") (pinfunction "PC3_P$74") (pintype "bidirectional"))
    )
    (net (code "154") (name "unconnected-(U$1D-PC13-PadP$68)") (class "Default")
      (node (ref "U$1") (pin "P$68") (pinfunction "PC13_P$68") (pintype "bidirectional"))
    )
    (net (code "155") (name "unconnected-(U$1D-PE2-PadP$63)") (class "Default")
      (node (ref "U$1") (pin "P$63") (pinfunction "PE2_P$63") (pintype "bidirectional"))
    )
    (net (code "156") (name "unconnected-(U$1D-PE3-PadP$64)") (class "Default")
      (node (ref "U$1") (pin "P$64") (pinfunction "PE3_P$64") (pintype "bidirectional"))
    )
    (net (code "157") (name "unconnected-(U$1D-PE4-PadP$65)") (class "Default")
      (node (ref "U$1") (pin "P$65") (pinfunction "PE4_P$65") (pintype "bidirectional"))
    )
    (net (code "158") (name "unconnected-(U$1D-PE5-PadP$66)") (class "Default")
      (node (ref "U$1") (pin "P$66") (pinfunction "PE5_P$66") (pintype "bidirectional"))
    )
    (net (code "159") (name "unconnected-(U$1D-PE6-PadP$67)") (class "Default")
      (node (ref "U$1") (pin "P$67") (pinfunction "PE6_P$67") (pintype "bidirectional"))
    )
    (net (code "160") (name "unconnected-(U$30-{slash}OUT15-Pad23)") (class "Default")
      (node (ref "U$30") (pin "23") (pinfunction "/OUT15_23") (pintype "bidirectional"))
    )
    (net (code "161") (name "unconnected-(U$33-{slash}OUT15-Pad23)") (class "Default")
      (node (ref "U$33") (pin "23") (pinfunction "/OUT15_23") (pintype "bidirectional"))
    )
    (net (code "162") (name "unconnected-(U$36-{slash}OUT15-Pad23)") (class "Default")
      (node (ref "U$36") (pin "23") (pinfunction "/OUT15_23") (pintype "bidirectional"))
    )
    (net (code "163") (name "unconnected-(U$51-{slash}OUT15-Pad23)") (class "Default")
      (node (ref "U$51") (pin "23") (pinfunction "/OUT15_23") (pintype "bidirectional"))
    )
  )
)
